# i2c.net
KiCad netlist of a schematic drawn in Altium Designer
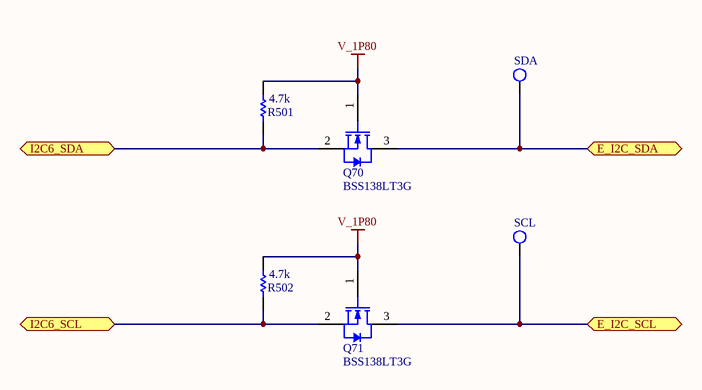
[diagram p0: i2c.SchDoc]

(export (version "E")
  (design (tool "Eeschema 10.0.6"))
  (components
    (comp (ref "Q70")
      (value "BSS138LT3G")
      (footprint "ONSC-SOT-23-3-318-08_V")
      (description "Power MOSFET, 200 mA, 50 V, N-Channel, 3-Pin SOT-23, Pb-Free, Tape and Reel")
      (fields (field (name "MANUFACTURER") "On Semiconductor"))
      (libsource (lib "Altium Content Vault") (part "CMP-1058-00765-1"))
    )
    (comp (ref "Q71")
      (value "BSS138LT3G")
      (footprint "ONSC-SOT-23-3-318-08_V")
      (description "Power MOSFET, 200 mA, 50 V, N-Channel, 3-Pin SOT-23, Pb-Free, Tape and Reel")
      (fields (field (name "MANUFACTURER") "On Semiconductor"))
      (libsource (lib "Altium Content Vault") (part "CMP-1058-00765-1"))
    )
    (comp (ref "R501")
      (value "4.7k")
      (footprint "RESC0603(1608)_N")
      (description "4K7 0.1W 5% 0603 (1608 Metric)  SMD")
      (fields (field (name "TOLERANCE") "5 %") (field (name "POWER") "0.1 W"))
      (libsource (lib "Altium Content Vault") (part "CMP-1012-00090-1"))
    )
    (comp (ref "R502")
      (value "4.7k")
      (footprint "RESC0603(1608)_N")
      (description "4K7 0.1W 5% 0603 (1608 Metric)  SMD")
      (fields (field (name "TOLERANCE") "5 %") (field (name "POWER") "0.1 W"))
      (libsource (lib "Altium Content Vault") (part "CMP-1012-00090-1"))
    )
    (comp (ref "SCL")
      (value "Testpoint")
      (footprint "Tespoint_Keystone")
      (libsource (lib "elevate_lib") (part "TestPoint"))
    )
    (comp (ref "SDA")
      (value "Testpoint")
      (footprint "Tespoint_Keystone")
      (libsource (lib "elevate_lib") (part "TestPoint"))
    )
  )
  (nets
    (net (code "1") (name "/E_I2C_SCL") (class "Default")
      (node (ref "Q71") (pin "3") (pinfunction "D_3") (pintype "passive"))
      (node (ref "SCL") (pin "1") (pinfunction "TP_1") (pintype "passive"))
    )
    (net (code "2") (name "/E_I2C_SDA") (class "Default")
      (node (ref "Q70") (pin "3") (pinfunction "D_3") (pintype "passive"))
      (node (ref "SDA") (pin "1") (pinfunction "TP_1") (pintype "passive"))
    )
    (net (code "3") (name "/I2C6_SCL") (class "Default")
      (node (ref "Q71") (pin "2") (pinfunction "S_2") (pintype "passive"))
      (node (ref "R502") (pin "1") (pinfunction "1_1") (pintype "passive"))
    )
    (net (code "4") (name "/I2C6_SDA") (class "Default")
      (node (ref "Q70") (pin "2") (pinfunction "S_2") (pintype "passive"))
      (node (ref "R501") (pin "1") (pinfunction "1_1") (pintype "passive"))
    )
    (net (code "5") (name "V_1P80") (class "Default")
      (node (ref "Q70") (pin "1") (pinfunction "G_1") (pintype "passive"))
      (node (ref "Q71") (pin "1") (pinfunction "G_1") (pintype "passive"))
      (node (ref "R501") (pin "2") (pinfunction "2_2") (pintype "passive"))
      (node (ref "R502") (pin "2") (pinfunction "2_2") (pintype "passive"))
    )
  )
)
